# SIM.net
KiCad netlist of a schematic drawn in Altium Designer
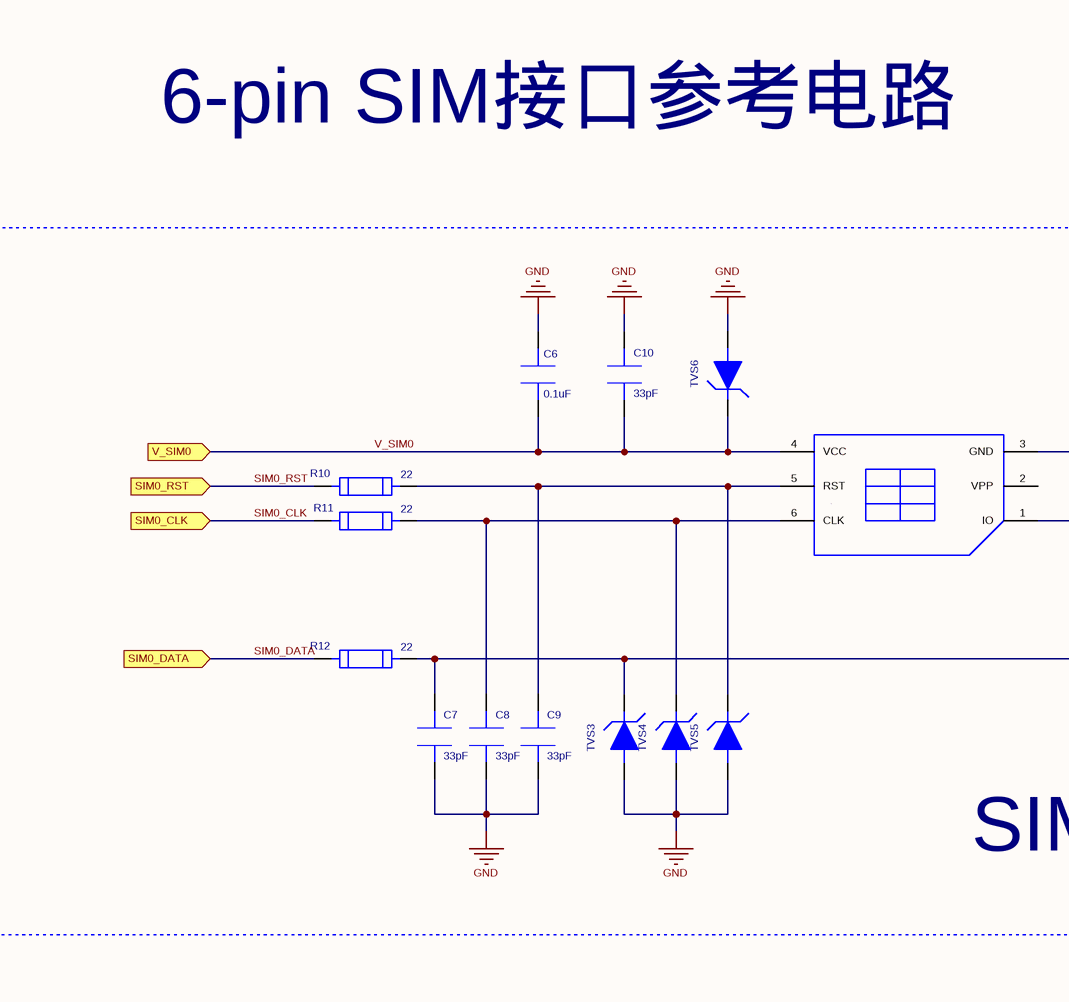
[diagram p0: SIM.SchDoc, top left]
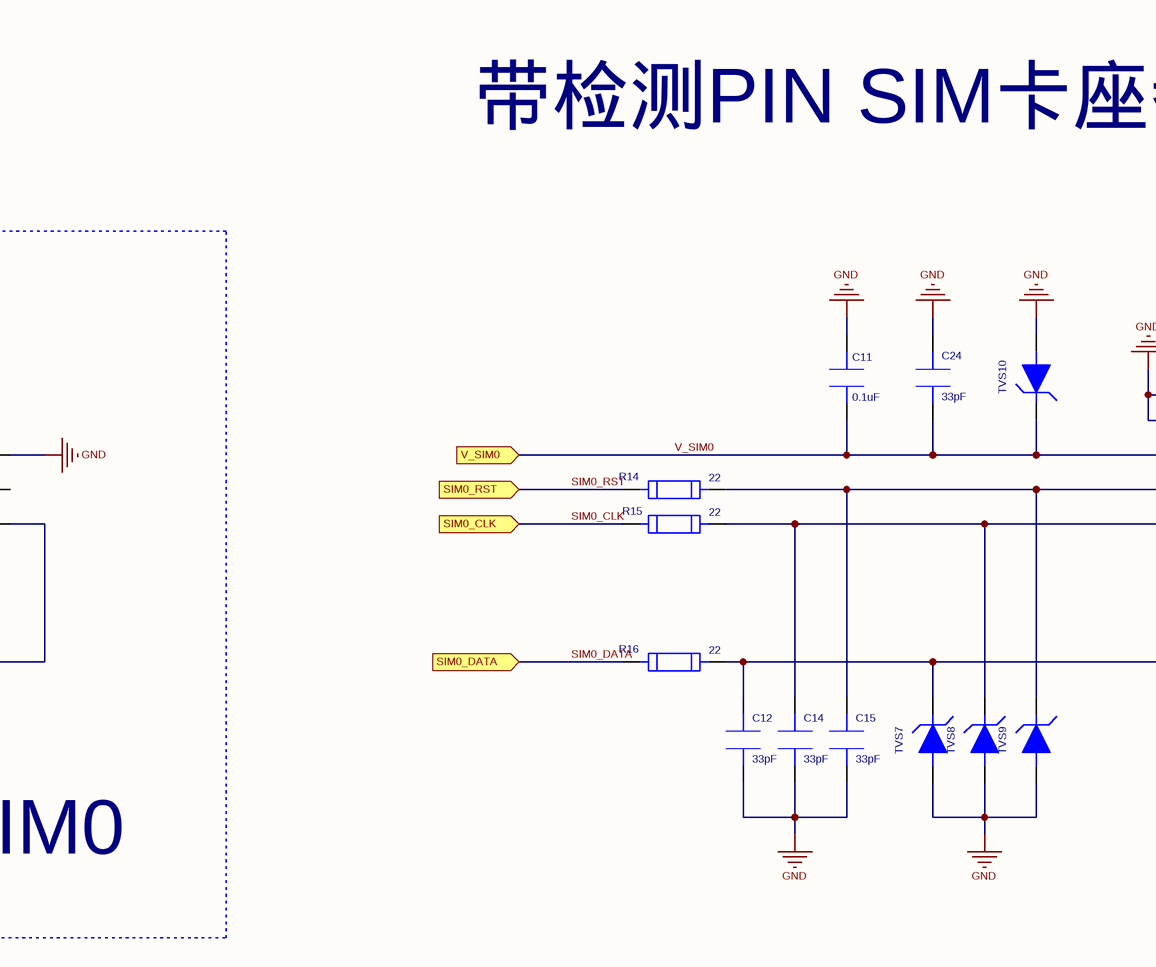
[diagram p1: SIM.SchDoc, top middle]
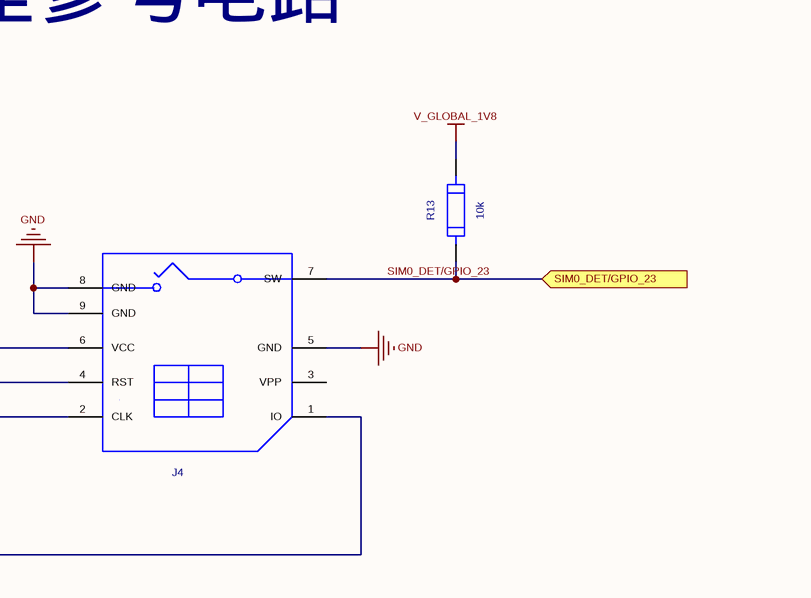
[diagram p2: SIM.SchDoc, top right]
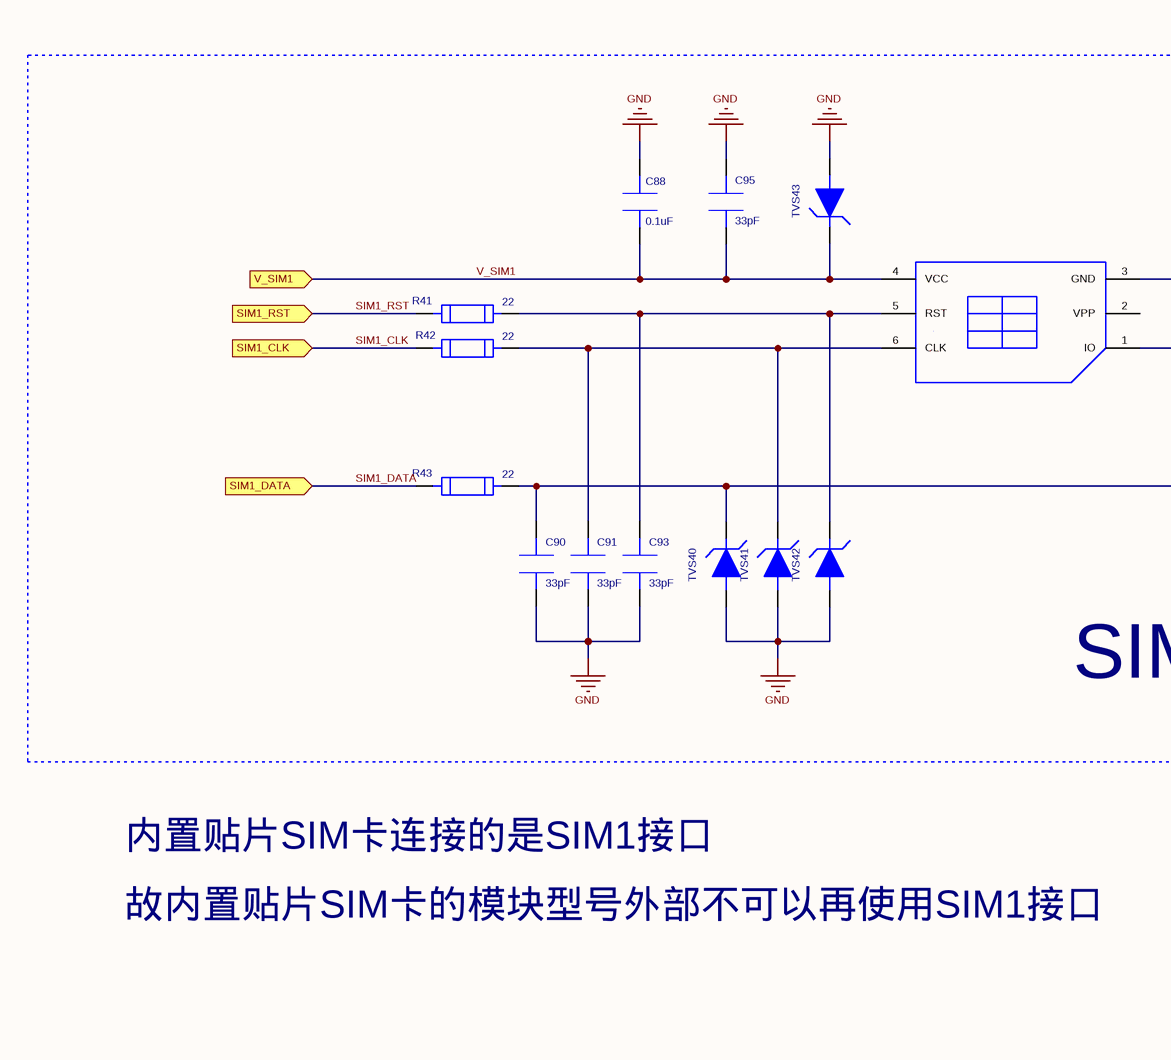
[diagram p3: SIM.SchDoc, bottom left]
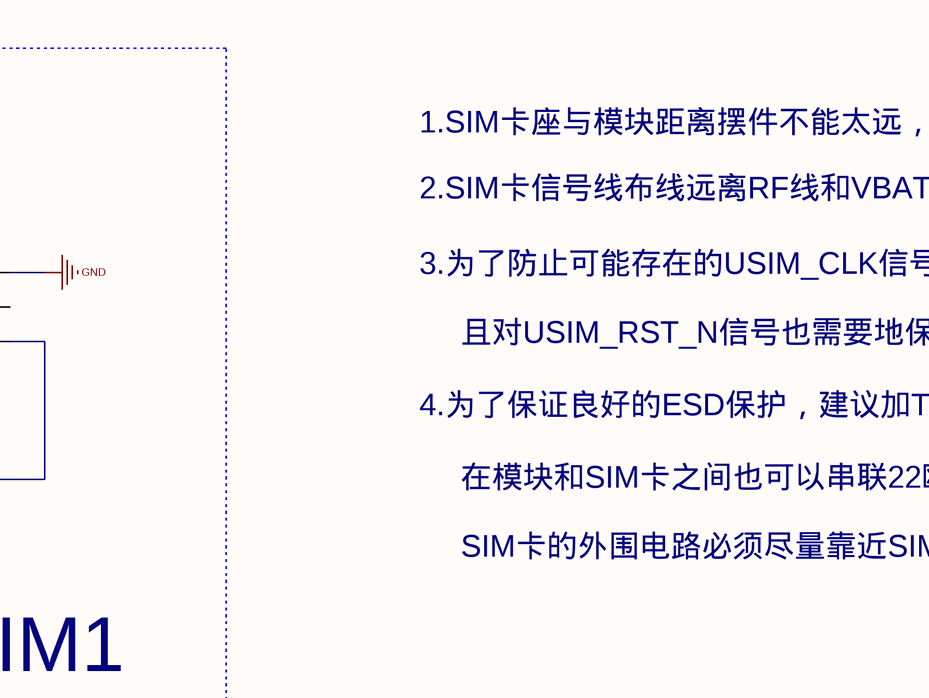
[diagram p4: SIM.SchDoc, bottom middle]
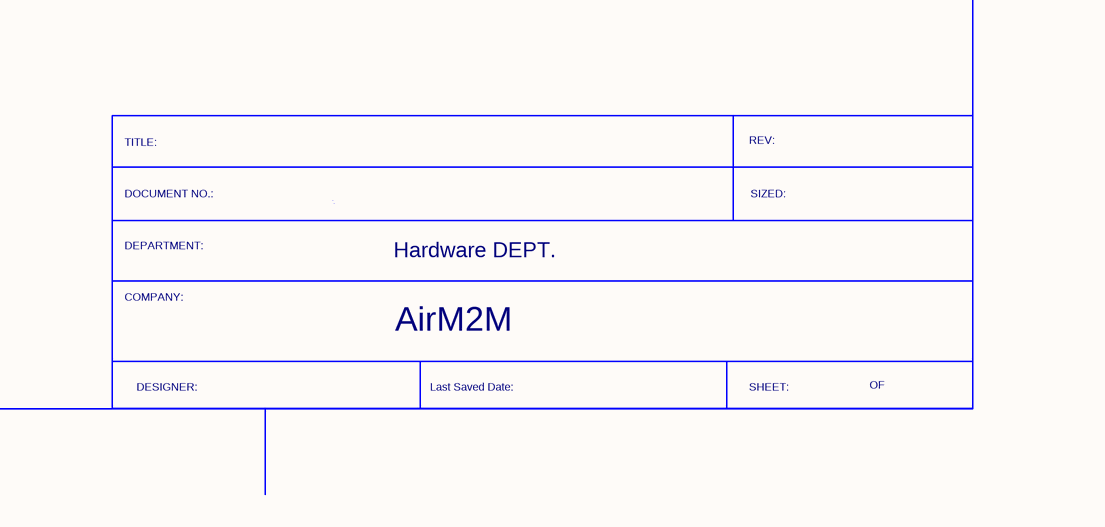
[diagram p5: SIM.SchDoc, bottom right]

(export (version "E")
  (design (tool "Eeschema 10.0.6"))
  (components
    (comp (ref "C6")
      (value "0.1uF")
      (footprint "SC0402")
      (description "CAP CER X5R/X7R;0.1uF;+/-10%;10V;0402;0.5mm;ROHS")
      (fields (field (name "TOLERANCE") "+/-10%") (field (name "Comment") "CAP-0.1UF-0402-X5R-10V"))
      (libsource (lib "*") (part "CAP-0.1UF-0402-X5R-10V"))
    )
    (comp (ref "C7")
      (value "33pF")
      (footprint "SC0402")
      (description "CAP CER C0G;33PF;+/-5%;50V;0402;0.5mm;ROHS")
      (fields (field (name "TOLERANCE") "+/-5%") (field (name "Comment") "CAP-33PF-0402-C0G"))
      (libsource (lib "*") (part "CAP-33PF-0402-C0G"))
    )
    (comp (ref "C8")
      (value "33pF")
      (footprint "SC0402")
      (description "CAP CER C0G;33PF;+/-5%;50V;0402;0.5mm;ROHS")
      (fields (field (name "TOLERANCE") "+/-5%") (field (name "Comment") "CAP-33PF-0402-C0G"))
      (libsource (lib "*") (part "CAP-33PF-0402-C0G"))
    )
    (comp (ref "C9")
      (value "33pF")
      (footprint "SC0402")
      (description "CAP CER C0G;33PF;+/-5%;50V;0402;0.5mm;ROHS")
      (fields (field (name "TOLERANCE") "+/-5%") (field (name "Comment") "CAP-33PF-0402-C0G"))
      (libsource (lib "*") (part "CAP-33PF-0402-C0G"))
    )
    (comp (ref "C10")
      (value "33pF")
      (footprint "SC0402")
      (description "CAP CER C0G;33PF;+/-5%;50V;0402;0.5mm;ROHS")
      (fields (field (name "TOLERANCE") "+/-5%") (field (name "Comment") "CAP-33PF-0402-C0G"))
      (libsource (lib "*") (part "CAP-33PF-0402-C0G"))
    )
    (comp (ref "C11")
      (value "0.1uF")
      (footprint "SC0402")
      (description "CAP CER X5R/X7R;0.1uF;+/-10%;10V;0402;0.5mm;ROHS")
      (fields (field (name "TOLERANCE") "+/-10%") (field (name "Comment") "CAP-0.1UF-0402-X5R-10V"))
      (libsource (lib "*") (part "CAP-0.1UF-0402-X5R-10V"))
    )
    (comp (ref "C12")
      (value "33pF")
      (footprint "SC0402")
      (description "CAP CER C0G;33PF;+/-5%;50V;0402;0.5mm;ROHS")
      (fields (field (name "TOLERANCE") "+/-5%") (field (name "Comment") "CAP-33PF-0402-C0G"))
      (libsource (lib "*") (part "CAP-33PF-0402-C0G"))
    )
    (comp (ref "C14")
      (value "33pF")
      (footprint "SC0402")
      (description "CAP CER C0G;33PF;+/-5%;50V;0402;0.5mm;ROHS")
      (fields (field (name "TOLERANCE") "+/-5%") (field (name "Comment") "CAP-33PF-0402-C0G"))
      (libsource (lib "*") (part "CAP-33PF-0402-C0G"))
    )
    (comp (ref "C15")
      (value "33pF")
      (footprint "SC0402")
      (description "CAP CER C0G;33PF;+/-5%;50V;0402;0.5mm;ROHS")
      (fields (field (name "TOLERANCE") "+/-5%") (field (name "Comment") "CAP-33PF-0402-C0G"))
      (libsource (lib "*") (part "CAP-33PF-0402-C0G"))
    )
    (comp (ref "C24")
      (value "33pF")
      (footprint "SC0402")
      (description "CAP CER C0G;33PF;+/-5%;50V;0402;0.5mm;ROHS")
      (fields (field (name "TOLERANCE") "+/-5%") (field (name "Comment") "CAP-33PF-0402-C0G"))
      (libsource (lib "*") (part "CAP-33PF-0402-C0G"))
    )
    (comp (ref "C88")
      (value "0.1uF")
      (footprint "SC0402")
      (description "CAP CER X5R/X7R;0.1uF;+/-10%;10V;0402;0.5mm;ROHS")
      (fields (field (name "TOLERANCE") "+/-10%") (field (name "Comment") "CAP-0.1UF-0402-X5R-10V"))
      (libsource (lib "*") (part "CAP-0.1UF-0402-X5R-10V"))
    )
    (comp (ref "C90")
      (value "33pF")
      (footprint "SC0402")
      (description "CAP CER C0G;33PF;+/-5%;50V;0402;0.5mm;ROHS")
      (fields (field (name "TOLERANCE") "+/-5%") (field (name "Comment") "CAP-33PF-0402-C0G"))
      (libsource (lib "*") (part "CAP-33PF-0402-C0G"))
    )
    (comp (ref "C91")
      (value "33pF")
      (footprint "SC0402")
      (description "CAP CER C0G;33PF;+/-5%;50V;0402;0.5mm;ROHS")
      (fields (field (name "TOLERANCE") "+/-5%") (field (name "Comment") "CAP-33PF-0402-C0G"))
      (libsource (lib "*") (part "CAP-33PF-0402-C0G"))
    )
    (comp (ref "C93")
      (value "33pF")
      (footprint "SC0402")
      (description "CAP CER C0G;33PF;+/-5%;50V;0402;0.5mm;ROHS")
      (fields (field (name "TOLERANCE") "+/-5%") (field (name "Comment") "CAP-33PF-0402-C0G"))
      (libsource (lib "*") (part "CAP-33PF-0402-C0G"))
    )
    (comp (ref "C95")
      (value "33pF")
      (footprint "SC0402")
      (description "CAP CER C0G;33PF;+/-5%;50V;0402;0.5mm;ROHS")
      (fields (field (name "TOLERANCE") "+/-5%") (field (name "Comment") "CAP-33PF-0402-C0G"))
      (libsource (lib "*") (part "CAP-33PF-0402-C0G"))
    )
    (comp (ref "J2")
      (value "SIMCARD6_1")
      (footprint "SIMCARD6")
      (description "SIM?座;6PIN;17.70*8.30*3.60mm;ROHS")
      (libsource (lib "*") (part "SIMCARD6_1"))
    )
    (comp (ref "J4")
      (value "SIM-SW-CAF98-06206-XX00")
      (footprint "SIM-SW-CAF98-06206-XX00")
      (description "SIM卡座;8PIN;PUSH TO PUSH;26.6*19.1*2.1mm;ROHS")
      (libsource (lib "*") (part "SIM-SW-CAF98-06206-XX00"))
    )
    (comp (ref "J10")
      (value "SIMCARD6_1")
      (footprint "SIMCARD6")
      (description "SIM?座;6PIN;17.70*8.30*3.60mm;ROHS")
      (libsource (lib "*") (part "SIMCARD6_1"))
    )
    (comp (ref "R10")
      (value "22")
      (footprint "SR0402")
      (description "RES FILM;22;+/-5%;1/16W;0402;0.4mm;ROHS")
      (fields (field (name "TOLERANCE") "+/-5%") (field (name "Comment") "RES-22-0402"))
      (libsource (lib "*") (part "RES-22-0402"))
    )
    (comp (ref "R11")
      (value "22")
      (footprint "SR0402")
      (description "RES FILM;22;+/-5%;1/16W;0402;0.4mm;ROHS")
      (fields (field (name "TOLERANCE") "+/-5%") (field (name "Comment") "RES-22-0402"))
      (libsource (lib "*") (part "RES-22-0402"))
    )
    (comp (ref "R12")
      (value "22")
      (footprint "SR0402")
      (description "RES FILM;22;+/-5%;1/16W;0402;0.4mm;ROHS")
      (fields (field (name "TOLERANCE") "+/-5%") (field (name "Comment") "RES-22-0402"))
      (libsource (lib "*") (part "RES-22-0402"))
    )
    (comp (ref "R13")
      (value "10k")
      (footprint "SR0402")
      (description "RES FILM;10K;+/-5%;1/16W;0402;0.4mm;ROHS")
      (fields (field (name "TOLERANCE") "+/-5%") (field (name "Comment") "RES-10K-0402"))
      (libsource (lib "*") (part "RES-10K-0402"))
    )
    (comp (ref "R14")
      (value "22")
      (footprint "SR0402")
      (description "RES FILM;22;+/-5%;1/16W;0402;0.4mm;ROHS")
      (fields (field (name "TOLERANCE") "+/-5%") (field (name "Comment") "RES-22-0402"))
      (libsource (lib "*") (part "RES-22-0402"))
    )
    (comp (ref "R15")
      (value "22")
      (footprint "SR0402")
      (description "RES FILM;22;+/-5%;1/16W;0402;0.4mm;ROHS")
      (fields (field (name "TOLERANCE") "+/-5%") (field (name "Comment") "RES-22-0402"))
      (libsource (lib "*") (part "RES-22-0402"))
    )
    (comp (ref "R16")
      (value "22")
      (footprint "SR0402")
      (description "RES FILM;22;+/-5%;1/16W;0402;0.4mm;ROHS")
      (fields (field (name "TOLERANCE") "+/-5%") (field (name "Comment") "RES-22-0402"))
      (libsource (lib "*") (part "RES-22-0402"))
    )
    (comp (ref "R41")
      (value "22")
      (footprint "SR0402")
      (description "RES FILM;22;+/-5%;1/16W;0402;0.4mm;ROHS")
      (fields (field (name "TOLERANCE") "+/-5%") (field (name "Comment") "RES-22-0402"))
      (libsource (lib "*") (part "RES-22-0402"))
    )
    (comp (ref "R42")
      (value "22")
      (footprint "SR0402")
      (description "RES FILM;22;+/-5%;1/16W;0402;0.4mm;ROHS")
      (fields (field (name "TOLERANCE") "+/-5%") (field (name "Comment") "RES-22-0402"))
      (libsource (lib "*") (part "RES-22-0402"))
    )
    (comp (ref "R43")
      (value "22")
      (footprint "SR0402")
      (description "RES FILM;22;+/-5%;1/16W;0402;0.4mm;ROHS")
      (fields (field (name "TOLERANCE") "+/-5%") (field (name "Comment") "RES-22-0402"))
      (libsource (lib "*") (part "RES-22-0402"))
    )
    (comp (ref "TVS3")
      (value "ESD-TVS-ESD9X5.0ST5G")
      (footprint "SOD-923-ESD9X5.0ST5G")
      (description "TVS;5.0V;65PF;SOD?923;ROHS")
      (libsource (lib "*") (part "ESD-TVS-ESD9X5.0ST5G"))
    )
    (comp (ref "TVS4")
      (value "ESD-TVS-ESD9X5.0ST5G")
      (footprint "SOD-923-ESD9X5.0ST5G")
      (description "TVS;5.0V;65PF;SOD?923;ROHS")
      (libsource (lib "*") (part "ESD-TVS-ESD9X5.0ST5G"))
    )
    (comp (ref "TVS5")
      (value "ESD-TVS-ESD9X5.0ST5G")
      (footprint "SOD-923-ESD9X5.0ST5G")
      (description "TVS;5.0V;65PF;SOD?923;ROHS")
      (libsource (lib "*") (part "ESD-TVS-ESD9X5.0ST5G"))
    )
    (comp (ref "TVS6")
      (value "ESD-TVS-ESD9X5.0ST5G")
      (footprint "SOD-923-ESD9X5.0ST5G")
      (description "TVS;5.0V;65PF;SOD?923;ROHS")
      (libsource (lib "*") (part "ESD-TVS-ESD9X5.0ST5G"))
    )
    (comp (ref "TVS7")
      (value "ESD-TVS-ESD9X5.0ST5G")
      (footprint "SOD-923-ESD9X5.0ST5G")
      (description "TVS;5.0V;65PF;SOD?923;ROHS")
      (libsource (lib "*") (part "ESD-TVS-ESD9X5.0ST5G"))
    )
    (comp (ref "TVS8")
      (value "ESD-TVS-ESD9X5.0ST5G")
      (footprint "SOD-923-ESD9X5.0ST5G")
      (description "TVS;5.0V;65PF;SOD?923;ROHS")
      (libsource (lib "*") (part "ESD-TVS-ESD9X5.0ST5G"))
    )
    (comp (ref "TVS9")
      (value "ESD-TVS-ESD9X5.0ST5G")
      (footprint "SOD-923-ESD9X5.0ST5G")
      (description "TVS;5.0V;65PF;SOD?923;ROHS")
      (libsource (lib "*") (part "ESD-TVS-ESD9X5.0ST5G"))
    )
    (comp (ref "TVS10")
      (value "ESD-TVS-ESD9X5.0ST5G")
      (footprint "SOD-923-ESD9X5.0ST5G")
      (description "TVS;5.0V;65PF;SOD?923;ROHS")
      (libsource (lib "*") (part "ESD-TVS-ESD9X5.0ST5G"))
    )
    (comp (ref "TVS40")
      (value "ESD-TVS-ESD9X5.0ST5G")
      (footprint "SOD-923-ESD9X5.0ST5G")
      (description "TVS;5.0V;65PF;SOD?923;ROHS")
      (libsource (lib "*") (part "ESD-TVS-ESD9X5.0ST5G"))
    )
    (comp (ref "TVS41")
      (value "ESD-TVS-ESD9X5.0ST5G")
      (footprint "SOD-923-ESD9X5.0ST5G")
      (description "TVS;5.0V;65PF;SOD?923;ROHS")
      (libsource (lib "*") (part "ESD-TVS-ESD9X5.0ST5G"))
    )
    (comp (ref "TVS42")
      (value "ESD-TVS-ESD9X5.0ST5G")
      (footprint "SOD-923-ESD9X5.0ST5G")
      (description "TVS;5.0V;65PF;SOD?923;ROHS")
      (libsource (lib "*") (part "ESD-TVS-ESD9X5.0ST5G"))
    )
    (comp (ref "TVS43")
      (value "ESD-TVS-ESD9X5.0ST5G")
      (footprint "SOD-923-ESD9X5.0ST5G")
      (description "TVS;5.0V;65PF;SOD?923;ROHS")
      (libsource (lib "*") (part "ESD-TVS-ESD9X5.0ST5G"))
    )
  )
  (nets
    (net (code "1") (name "/SIM0_CLK") (class "Default")
      (node (ref "R11") (pin "1") (pinfunction "1_1") (pintype "passive"))
      (node (ref "R15") (pin "1") (pinfunction "1_1") (pintype "passive"))
    )
    (net (code "2") (name "/SIM0_DATA") (class "Default")
      (node (ref "R12") (pin "1") (pinfunction "1_1") (pintype "passive"))
      (node (ref "R16") (pin "1") (pinfunction "1_1") (pintype "passive"))
    )
    (net (code "3") (name "/SIM0_DET{slash}GPIO_23") (class "Default")
      (node (ref "J4") (pin "7") (pinfunction "SW_7") (pintype "passive"))
      (node (ref "R13") (pin "1") (pinfunction "1_1") (pintype "passive"))
    )
    (net (code "4") (name "/SIM0_RST") (class "Default")
      (node (ref "R10") (pin "1") (pinfunction "1_1") (pintype "passive"))
      (node (ref "R14") (pin "1") (pinfunction "1_1") (pintype "passive"))
    )
    (net (code "5") (name "/SIM1_CLK") (class "Default")
      (node (ref "R42") (pin "1") (pinfunction "1_1") (pintype "passive"))
    )
    (net (code "6") (name "/SIM1_DATA") (class "Default")
      (node (ref "R43") (pin "1") (pinfunction "1_1") (pintype "passive"))
    )
    (net (code "7") (name "/SIM1_RST") (class "Default")
      (node (ref "R41") (pin "1") (pinfunction "1_1") (pintype "passive"))
    )
    (net (code "8") (name "/V_SIM0") (class "Default")
      (node (ref "C10") (pin "2") (pinfunction "2_2") (pintype "passive"))
      (node (ref "C11") (pin "1") (pinfunction "1_1") (pintype "passive"))
      (node (ref "C24") (pin "2") (pinfunction "2_2") (pintype "passive"))
      (node (ref "C6") (pin "1") (pinfunction "1_1") (pintype "passive"))
      (node (ref "J2") (pin "4") (pinfunction "VCC_4") (pintype "passive"))
      (node (ref "J4") (pin "6") (pinfunction "VCC_6") (pintype "passive"))
      (node (ref "TVS10") (pin "1") (pinfunction "1_1") (pintype "passive"))
      (node (ref "TVS6") (pin "1") (pinfunction "1_1") (pintype "passive"))
    )
    (net (code "9") (name "/V_SIM1") (class "Default")
      (node (ref "C88") (pin "1") (pinfunction "1_1") (pintype "passive"))
      (node (ref "C95") (pin "2") (pinfunction "2_2") (pintype "passive"))
      (node (ref "J10") (pin "4") (pinfunction "VCC_4") (pintype "passive"))
      (node (ref "TVS43") (pin "1") (pinfunction "1_1") (pintype "passive"))
    )
    (net (code "10") (name "GND") (class "Default")
      (node (ref "C10") (pin "1") (pinfunction "1_1") (pintype "passive"))
      (node (ref "C11") (pin "2") (pinfunction "2_2") (pintype "passive"))
      (node (ref "C12") (pin "2") (pinfunction "2_2") (pintype "passive"))
      (node (ref "C14") (pin "2") (pinfunction "2_2") (pintype "passive"))
      (node (ref "C15") (pin "2") (pinfunction "2_2") (pintype "passive"))
      (node (ref "C24") (pin "1") (pinfunction "1_1") (pintype "passive"))
      (node (ref "C6") (pin "2") (pinfunction "2_2") (pintype "passive"))
      (node (ref "C7") (pin "2") (pinfunction "2_2") (pintype "passive"))
      (node (ref "C8") (pin "2") (pinfunction "2_2") (pintype "passive"))
      (node (ref "C88") (pin "2") (pinfunction "2_2") (pintype "passive"))
      (node (ref "C9") (pin "2") (pinfunction "2_2") (pintype "passive"))
      (node (ref "C90") (pin "2") (pinfunction "2_2") (pintype "passive"))
      (node (ref "C91") (pin "2") (pinfunction "2_2") (pintype "passive"))
      (node (ref "C93") (pin "2") (pinfunction "2_2") (pintype "passive"))
      (node (ref "C95") (pin "1") (pinfunction "1_1") (pintype "passive"))
      (node (ref "J10") (pin "3") (pinfunction "GND_3") (pintype "passive"))
      (node (ref "J2") (pin "3") (pinfunction "GND_3") (pintype "passive"))
      (node (ref "J4") (pin "5") (pinfunction "GND_5") (pintype "passive"))
      (node (ref "J4") (pin "8") (pinfunction "GND_8") (pintype "passive"))
      (node (ref "J4") (pin "9") (pinfunction "GND_9") (pintype "passive"))
      (node (ref "TVS10") (pin "2") (pinfunction "2_2") (pintype "passive"))
      (node (ref "TVS3") (pin "2") (pinfunction "2_2") (pintype "passive"))
      (node (ref "TVS4") (pin "2") (pinfunction "2_2") (pintype "passive"))
      (node (ref "TVS40") (pin "2") (pinfunction "2_2") (pintype "passive"))
      (node (ref "TVS41") (pin "2") (pinfunction "2_2") (pintype "passive"))
      (node (ref "TVS42") (pin "2") (pinfunction "2_2") (pintype "passive"))
      (node (ref "TVS43") (pin "2") (pinfunction "2_2") (pintype "passive"))
      (node (ref "TVS5") (pin "2") (pinfunction "2_2") (pintype "passive"))
      (node (ref "TVS6") (pin "2") (pinfunction "2_2") (pintype "passive"))
      (node (ref "TVS7") (pin "2") (pinfunction "2_2") (pintype "passive"))
      (node (ref "TVS8") (pin "2") (pinfunction "2_2") (pintype "passive"))
      (node (ref "TVS9") (pin "2") (pinfunction "2_2") (pintype "passive"))
    )
    (net (code "11") (name "Net-(J2-CLK)") (class "Default")
      (node (ref "C8") (pin "1") (pinfunction "1_1") (pintype "passive"))
      (node (ref "J2") (pin "6") (pinfunction "CLK_6") (pintype "passive"))
      (node (ref "R11") (pin "2") (pinfunction "2_2") (pintype "passive"))
      (node (ref "TVS4") (pin "1") (pinfunction "1_1") (pintype "passive"))
    )
    (net (code "12") (name "Net-(J2-IO)") (class "Default")
      (node (ref "C7") (pin "1") (pinfunction "1_1") (pintype "passive"))
      (node (ref "J2") (pin "1") (pinfunction "IO_1") (pintype "passive"))
      (node (ref "R12") (pin "2") (pinfunction "2_2") (pintype "passive"))
      (node (ref "TVS3") (pin "1") (pinfunction "1_1") (pintype "passive"))
    )
    (net (code "13") (name "Net-(J2-RST)") (class "Default")
      (node (ref "C9") (pin "1") (pinfunction "1_1") (pintype "passive"))
      (node (ref "J2") (pin "5") (pinfunction "RST_5") (pintype "passive"))
      (node (ref "R10") (pin "2") (pinfunction "2_2") (pintype "passive"))
      (node (ref "TVS5") (pin "1") (pinfunction "1_1") (pintype "passive"))
    )
    (net (code "14") (name "Net-(J4-CLK)") (class "Default")
      (node (ref "C14") (pin "1") (pinfunction "1_1") (pintype "passive"))
      (node (ref "J4") (pin "2") (pinfunction "CLK_2") (pintype "passive"))
      (node (ref "R15") (pin "2") (pinfunction "2_2") (pintype "passive"))
      (node (ref "TVS8") (pin "1") (pinfunction "1_1") (pintype "passive"))
    )
    (net (code "15") (name "Net-(J4-IO)") (class "Default")
      (node (ref "C12") (pin "1") (pinfunction "1_1") (pintype "passive"))
      (node (ref "J4") (pin "1") (pinfunction "IO_1") (pintype "passive"))
      (node (ref "R16") (pin "2") (pinfunction "2_2") (pintype "passive"))
      (node (ref "TVS7") (pin "1") (pinfunction "1_1") (pintype "passive"))
    )
    (net (code "16") (name "Net-(J4-RST)") (class "Default")
      (node (ref "C15") (pin "1") (pinfunction "1_1") (pintype "passive"))
      (node (ref "J4") (pin "4") (pinfunction "RST_4") (pintype "passive"))
      (node (ref "R14") (pin "2") (pinfunction "2_2") (pintype "passive"))
      (node (ref "TVS9") (pin "1") (pinfunction "1_1") (pintype "passive"))
    )
    (net (code "17") (name "Net-(J10-CLK)") (class "Default")
      (node (ref "C91") (pin "1") (pinfunction "1_1") (pintype "passive"))
      (node (ref "J10") (pin "6") (pinfunction "CLK_6") (pintype "passive"))
      (node (ref "R42") (pin "2") (pinfunction "2_2") (pintype "passive"))
      (node (ref "TVS41") (pin "1") (pinfunction "1_1") (pintype "passive"))
    )
    (net (code "18") (name "Net-(J10-IO)") (class "Default")
      (node (ref "C90") (pin "1") (pinfunction "1_1") (pintype "passive"))
      (node (ref "J10") (pin "1") (pinfunction "IO_1") (pintype "passive"))
      (node (ref "R43") (pin "2") (pinfunction "2_2") (pintype "passive"))
      (node (ref "TVS40") (pin "1") (pinfunction "1_1") (pintype "passive"))
    )
    (net (code "19") (name "Net-(J10-RST)") (class "Default")
      (node (ref "C93") (pin "1") (pinfunction "1_1") (pintype "passive"))
      (node (ref "J10") (pin "5") (pinfunction "RST_5") (pintype "passive"))
      (node (ref "R41") (pin "2") (pinfunction "2_2") (pintype "passive"))
      (node (ref "TVS42") (pin "1") (pinfunction "1_1") (pintype "passive"))
    )
    (net (code "20") (name "V_GLOBAL_1V8") (class "Default")
      (node (ref "R13") (pin "2") (pinfunction "2_2") (pintype "passive"))
    )
    (net (code "21") (name "unconnected-(J2-VPP-Pad2)") (class "Default")
      (node (ref "J2") (pin "2") (pinfunction "VPP_2") (pintype "passive"))
    )
    (net (code "22") (name "unconnected-(J4-VPP-Pad3)") (class "Default")
      (node (ref "J4") (pin "3") (pinfunction "VPP_3") (pintype "passive"))
    )
    (net (code "23") (name "unconnected-(J10-VPP-Pad2)") (class "Default")
      (node (ref "J10") (pin "2") (pinfunction "VPP_2") (pintype "passive"))
    )
  )
)
